# RS232_SelfPowered_Opto.net
KiCad netlist of a schematic drawn in EAGLE
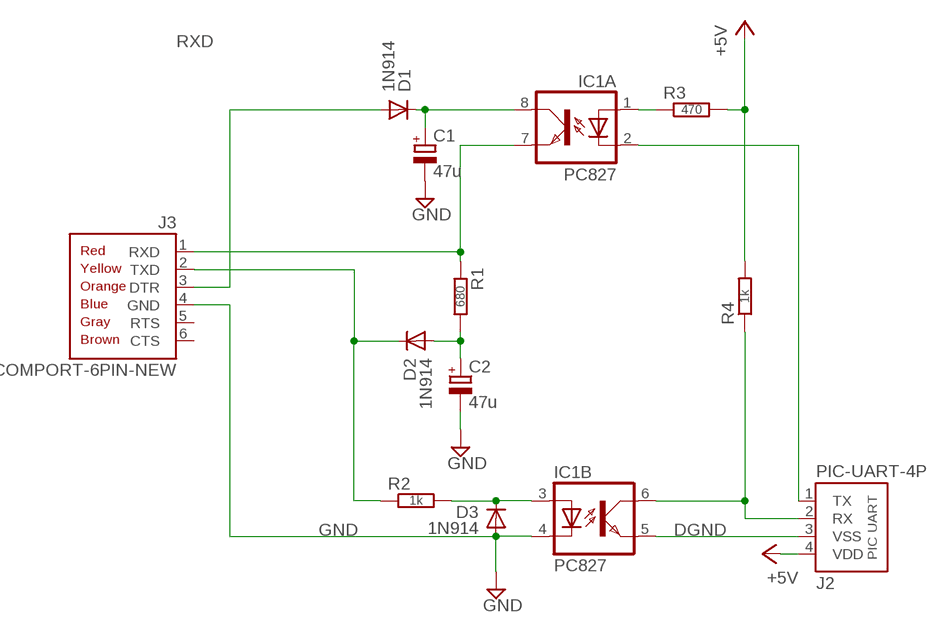
[diagram p0: schematic, sheet 1]

(export (version "E")
  (design (tool "Eeschema 10.0.6"))
  (components
    (comp (ref "C1")
      (value "47u")
      (footprint "eagle-import:E2,5-5")
      (libsource (lib "eagle-import") (part "CPOL-EUE2.5-5"))
    )
    (comp (ref "C2")
      (value "47u")
      (footprint "eagle-import:E2,5-5")
      (libsource (lib "eagle-import") (part "CPOL-EUE2.5-5"))
    )
    (comp (ref "D1")
      (value "1N914")
      (footprint "eagle-import:DO34-7V")
      (libsource (lib "eagle-import") (part "1N414834-7V"))
    )
    (comp (ref "D2")
      (value "1N914")
      (footprint "eagle-import:DO34-7")
      (libsource (lib "eagle-import") (part "1N414834-7"))
    )
    (comp (ref "D3")
      (value "1N914")
      (footprint "eagle-import:DO34-7V")
      (libsource (lib "eagle-import") (part "1N414834-7V"))
    )
    (comp (ref "IC1")
      (value "PC827")
      (footprint "eagle-import:DIL08")
      (libsource (lib "eagle-import") (part "ACPL-827"))
    )
    (comp (ref "J2")
      (value "PIC-UART-4P")
      (footprint "eagle-import:CONN-4P")
      (libsource (lib "eagle-import") (part "PIC-UART-4P"))
    )
    (comp (ref "J3")
      (value "COMPORT-6PIN-NEW")
      (footprint "eagle-import:RS232-6PIN-NEW")
      (libsource (lib "eagle-import") (part "COMPORT-6PIN-NEW"))
    )
    (comp (ref "R1")
      (value "680")
      (footprint "eagle-import:0202_7")
      (libsource (lib "eagle-import") (part "R0202/7"))
    )
    (comp (ref "R2")
      (value "1k")
      (footprint "eagle-import:0202_7")
      (libsource (lib "eagle-import") (part "R0202/7"))
    )
    (comp (ref "R3")
      (value "470")
      (footprint "eagle-import:0202_10-V")
      (libsource (lib "eagle-import") (part "R0202/10-V"))
    )
    (comp (ref "R4")
      (value "1k")
      (footprint "eagle-import:0202_7-V")
      (libsource (lib "eagle-import") (part "R0202/7-V"))
    )
  )
  (nets
    (net (code "1") (name "+5V") (class "Default")
      (node (ref "J2") (pin "4") (pinfunction "VDD_4") (pintype "passive"))
      (node (ref "R3") (pin "2") (pinfunction "2_2") (pintype "passive"))
      (node (ref "R4") (pin "2") (pinfunction "2_2") (pintype "passive"))
    )
    (net (code "2") (name "/DGND") (class "Default")
      (node (ref "IC1") (pin "5") (pinfunction "EMIT_5") (pintype "passive"))
      (node (ref "J2") (pin "3") (pinfunction "VSS_3") (pintype "passive"))
    )
    (net (code "3") (name "/RXD") (class "Default")
      (node (ref "IC1") (pin "7") (pinfunction "EMIT_7") (pintype "passive"))
      (node (ref "J3") (pin "1") (pinfunction "RXD_1") (pintype "passive"))
      (node (ref "R1") (pin "1") (pinfunction "1_1") (pintype "passive"))
    )
    (net (code "4") (name "GND") (class "Default")
      (node (ref "C1") (pin "-") (pinfunction "-_-") (pintype "passive"))
      (node (ref "C2") (pin "-") (pinfunction "-_-") (pintype "passive"))
      (node (ref "D3") (pin "A") (pinfunction "A_A") (pintype "passive"))
      (node (ref "IC1") (pin "4") (pinfunction "C_4") (pintype "passive"))
      (node (ref "J3") (pin "4") (pinfunction "GND_4") (pintype "passive"))
    )
    (net (code "5") (name "Net-(C2-Pad+)") (class "Default")
      (node (ref "C2") (pin "+") (pinfunction "+_+") (pintype "passive"))
      (node (ref "D2") (pin "A") (pinfunction "A_A") (pintype "passive"))
      (node (ref "R1") (pin "2") (pinfunction "2_2") (pintype "passive"))
    )
    (net (code "6") (name "Net-(IC1A-A)") (class "Default")
      (node (ref "IC1") (pin "1") (pinfunction "A_1") (pintype "passive"))
      (node (ref "R3") (pin "1") (pinfunction "1_1") (pintype "passive"))
    )
    (net (code "7") (name "Net-(IC1A-C)") (class "Default")
      (node (ref "IC1") (pin "2") (pinfunction "C_2") (pintype "passive"))
      (node (ref "J2") (pin "1") (pinfunction "TX_1") (pintype "passive"))
    )
    (net (code "8") (name "Net-(IC1A-COL)") (class "Default")
      (node (ref "C1") (pin "+") (pinfunction "+_+") (pintype "passive"))
      (node (ref "D1") (pin "C") (pinfunction "C_C") (pintype "passive"))
      (node (ref "IC1") (pin "8") (pinfunction "COL_8") (pintype "passive"))
    )
    (net (code "9") (name "Net-(IC1B-A)") (class "Default")
      (node (ref "D3") (pin "C") (pinfunction "C_C") (pintype "passive"))
      (node (ref "IC1") (pin "3") (pinfunction "A_3") (pintype "passive"))
      (node (ref "R2") (pin "2") (pinfunction "2_2") (pintype "passive"))
    )
    (net (code "10") (name "Net-(IC1B-COL)") (class "Default")
      (node (ref "IC1") (pin "6") (pinfunction "COL_6") (pintype "passive"))
      (node (ref "J2") (pin "2") (pinfunction "RX_2") (pintype "passive"))
      (node (ref "R4") (pin "1") (pinfunction "1_1") (pintype "passive"))
    )
    (net (code "11") (name "Net-(J3-DTR)") (class "Default")
      (node (ref "D1") (pin "A") (pinfunction "A_A") (pintype "passive"))
      (node (ref "J3") (pin "3") (pinfunction "DTR_3") (pintype "passive"))
    )
    (net (code "12") (name "Net-(J3-TXD)") (class "Default")
      (node (ref "D2") (pin "C") (pinfunction "C_C") (pintype "passive"))
      (node (ref "J3") (pin "2") (pinfunction "TXD_2") (pintype "passive"))
      (node (ref "R2") (pin "1") (pinfunction "1_1") (pintype "passive"))
    )
    (net (code "13") (name "unconnected-(J3-CTS-Pad6)") (class "Default")
      (node (ref "J3") (pin "6") (pinfunction "CTS_6") (pintype "passive"))
    )
    (net (code "14") (name "unconnected-(J3-RTS-Pad5)") (class "Default")
      (node (ref "J3") (pin "5") (pinfunction "RTS_5") (pintype "passive"))
    )
  )
)
